# Arduino_SST39SF040_Programmer_Shield_202.net
KiCad netlist of a schematic drawn in EasyEDA
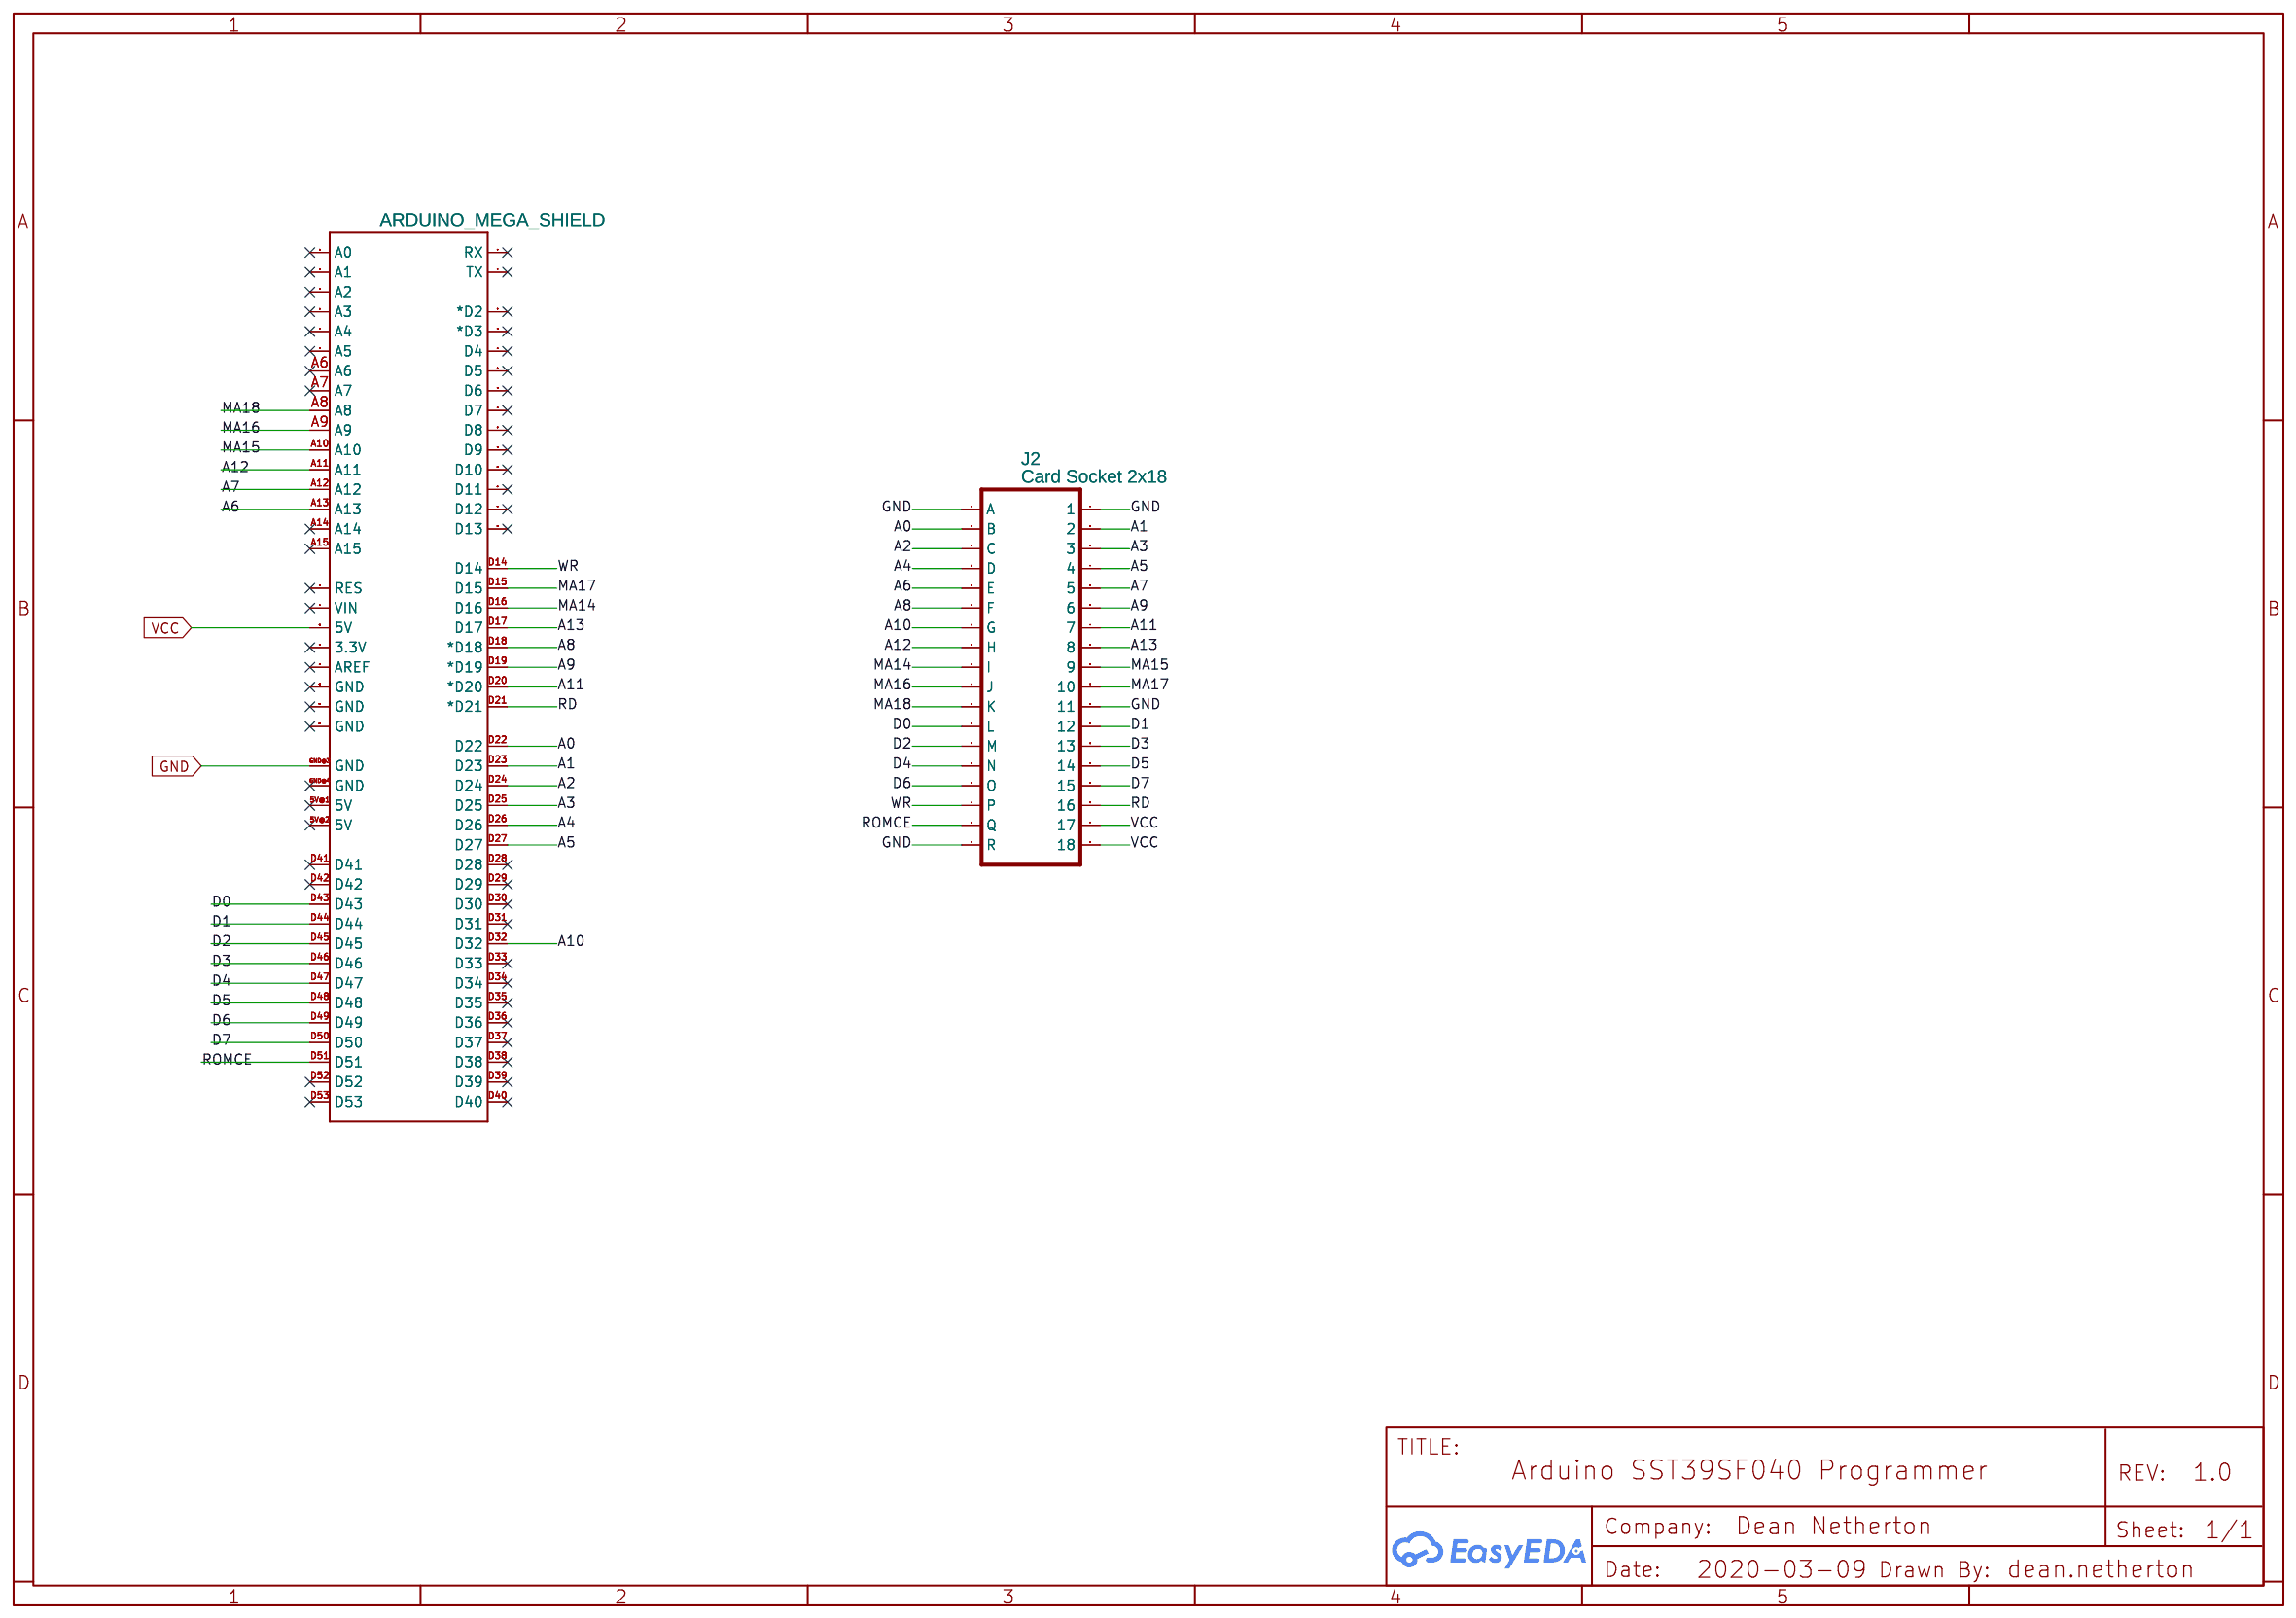
[diagram p0: schematic sheet]

(export (version "E")
  (design (tool "Eeschema 10.0.6"))
  (components
    (comp (ref "J2") (value "Card Socket 2x18") (libsource (lib "") (part "Card Socket 2x18")))
    (comp (ref "U2") (value "ARDUINO_MEGA_SHIELD") (libsource (lib "") (part "ARDUINO_MEGA_SHIELD")))
  )
  (nets
    (net (code "1") (name "/A0") (class "Default")
      (node (ref "J2") (pin "B") (pinfunction "B_B") (pintype "unspecified"))
      (node (ref "U2") (pin "D22") (pinfunction "D22_D22") (pintype "unspecified"))
    )
    (net (code "2") (name "/A1") (class "Default")
      (node (ref "J2") (pin "2") (pinfunction "2_2") (pintype "unspecified"))
      (node (ref "U2") (pin "D23") (pinfunction "D23_D23") (pintype "unspecified"))
    )
    (net (code "3") (name "/A2") (class "Default")
      (node (ref "J2") (pin "C") (pinfunction "C_C") (pintype "unspecified"))
      (node (ref "U2") (pin "D24") (pinfunction "D24_D24") (pintype "unspecified"))
    )
    (net (code "4") (name "/A3") (class "Default")
      (node (ref "J2") (pin "3") (pinfunction "3_3") (pintype "unspecified"))
      (node (ref "U2") (pin "D25") (pinfunction "D25_D25") (pintype "unspecified"))
    )
    (net (code "5") (name "/A4") (class "Default")
      (node (ref "J2") (pin "D") (pinfunction "D_D") (pintype "unspecified"))
      (node (ref "U2") (pin "D26") (pinfunction "D26_D26") (pintype "unspecified"))
    )
    (net (code "6") (name "/A5") (class "Default")
      (node (ref "J2") (pin "4") (pinfunction "4_4") (pintype "unspecified"))
      (node (ref "U2") (pin "D27") (pinfunction "D27_D27") (pintype "unspecified"))
    )
    (net (code "7") (name "/A6") (class "Default")
      (node (ref "J2") (pin "E") (pinfunction "E_E") (pintype "unspecified"))
      (node (ref "U2") (pin "A13") (pinfunction "A13_A13") (pintype "unspecified"))
    )
    (net (code "8") (name "/A7") (class "Default")
      (node (ref "J2") (pin "5") (pinfunction "5_5") (pintype "unspecified"))
      (node (ref "U2") (pin "A12") (pinfunction "A12_A12") (pintype "unspecified"))
    )
    (net (code "9") (name "/A8") (class "Default")
      (node (ref "J2") (pin "F") (pinfunction "F_F") (pintype "unspecified"))
      (node (ref "U2") (pin "D18") (pinfunction "*D18_D18") (pintype "unspecified"))
    )
    (net (code "10") (name "/A9") (class "Default")
      (node (ref "J2") (pin "6") (pinfunction "6_6") (pintype "unspecified"))
      (node (ref "U2") (pin "D19") (pinfunction "*D19_D19") (pintype "unspecified"))
    )
    (net (code "11") (name "/A10") (class "Default")
      (node (ref "J2") (pin "H") (pinfunction "G_H") (pintype "unspecified"))
      (node (ref "U2") (pin "D32") (pinfunction "D32_D32") (pintype "unspecified"))
    )
    (net (code "12") (name "/A11") (class "Default")
      (node (ref "J2") (pin "7") (pinfunction "7_7") (pintype "unspecified"))
      (node (ref "U2") (pin "D20") (pinfunction "*D20_D20") (pintype "unspecified"))
    )
    (net (code "13") (name "/A12") (class "Default")
      (node (ref "J2") (pin "J") (pinfunction "H_J") (pintype "unspecified"))
      (node (ref "U2") (pin "A11") (pinfunction "A11_A11") (pintype "unspecified"))
    )
    (net (code "14") (name "/A13") (class "Default")
      (node (ref "J2") (pin "8") (pinfunction "8_8") (pintype "unspecified"))
      (node (ref "U2") (pin "D17") (pinfunction "D17_D17") (pintype "unspecified"))
    )
    (net (code "15") (name "/D0") (class "Default")
      (node (ref "J2") (pin "N") (pinfunction "L_N") (pintype "unspecified"))
      (node (ref "U2") (pin "D43") (pinfunction "D43_D43") (pintype "unspecified"))
    )
    (net (code "16") (name "/D1") (class "Default")
      (node (ref "J2") (pin "12") (pinfunction "12_12") (pintype "unspecified"))
      (node (ref "U2") (pin "D44") (pinfunction "D44_D44") (pintype "unspecified"))
    )
    (net (code "17") (name "/D2") (class "Default")
      (node (ref "J2") (pin "P") (pinfunction "M_P") (pintype "unspecified"))
      (node (ref "U2") (pin "D45") (pinfunction "D45_D45") (pintype "unspecified"))
    )
    (net (code "18") (name "/D3") (class "Default")
      (node (ref "J2") (pin "13") (pinfunction "13_13") (pintype "unspecified"))
      (node (ref "U2") (pin "D46") (pinfunction "D46_D46") (pintype "unspecified"))
    )
    (net (code "19") (name "/D4") (class "Default")
      (node (ref "J2") (pin "R") (pinfunction "N_R") (pintype "unspecified"))
      (node (ref "U2") (pin "D47") (pinfunction "D47_D47") (pintype "unspecified"))
    )
    (net (code "20") (name "/D5") (class "Default")
      (node (ref "J2") (pin "14") (pinfunction "14_14") (pintype "unspecified"))
      (node (ref "U2") (pin "D48") (pinfunction "D48_D48") (pintype "unspecified"))
    )
    (net (code "21") (name "/D6") (class "Default")
      (node (ref "J2") (pin "S") (pinfunction "O_S") (pintype "unspecified"))
      (node (ref "U2") (pin "D49") (pinfunction "D49_D49") (pintype "unspecified"))
    )
    (net (code "22") (name "/D7") (class "Default")
      (node (ref "J2") (pin "15") (pinfunction "15_15") (pintype "unspecified"))
      (node (ref "U2") (pin "D50") (pinfunction "D50_D50") (pintype "unspecified"))
    )
    (net (code "23") (name "/MA14") (class "Default")
      (node (ref "J2") (pin "K") (pinfunction "I_K") (pintype "unspecified"))
      (node (ref "U2") (pin "D16") (pinfunction "D16_D16") (pintype "unspecified"))
    )
    (net (code "24") (name "/MA15") (class "Default")
      (node (ref "J2") (pin "9") (pinfunction "9_9") (pintype "unspecified"))
      (node (ref "U2") (pin "A10") (pinfunction "A10_A10") (pintype "unspecified"))
    )
    (net (code "25") (name "/MA16") (class "Default")
      (node (ref "J2") (pin "L") (pinfunction "J_L") (pintype "unspecified"))
      (node (ref "U2") (pin "A9") (pinfunction "A9_A9") (pintype "unspecified"))
    )
    (net (code "26") (name "/MA17") (class "Default")
      (node (ref "J2") (pin "10") (pinfunction "10_10") (pintype "unspecified"))
      (node (ref "U2") (pin "D15") (pinfunction "D15_D15") (pintype "unspecified"))
    )
    (net (code "27") (name "/MA18") (class "Default")
      (node (ref "J2") (pin "M") (pinfunction "K_M") (pintype "unspecified"))
      (node (ref "U2") (pin "A8") (pinfunction "A8_A8") (pintype "unspecified"))
    )
    (net (code "28") (name "/RD") (class "Default")
      (node (ref "J2") (pin "16") (pinfunction "16_16") (pintype "unspecified"))
      (node (ref "U2") (pin "D21") (pinfunction "*D21_D21") (pintype "unspecified"))
    )
    (net (code "29") (name "/ROMCE") (class "Default")
      (node (ref "J2") (pin "U") (pinfunction "Q_U") (pintype "unspecified"))
      (node (ref "U2") (pin "D51") (pinfunction "D51_D51") (pintype "unspecified"))
    )
    (net (code "30") (name "/WR") (class "Default")
      (node (ref "J2") (pin "T") (pinfunction "P_T") (pintype "unspecified"))
      (node (ref "U2") (pin "D14") (pinfunction "D14_D14") (pintype "unspecified"))
    )
    (net (code "31") (name "GND") (class "Default")
      (node (ref "J2") (pin "1") (pinfunction "1_1") (pintype "unspecified"))
      (node (ref "J2") (pin "11") (pinfunction "11_11") (pintype "unspecified"))
      (node (ref "J2") (pin "A") (pinfunction "A_A") (pintype "unspecified"))
      (node (ref "J2") (pin "V") (pinfunction "R_V") (pintype "unspecified"))
      (node (ref "U2") (pin "GND@3") (pinfunction "GND_GND@3") (pintype "unspecified"))
    )
    (net (code "32") (name "VCC") (class "Default")
      (node (ref "J2") (pin "17") (pinfunction "17_17") (pintype "unspecified"))
      (node (ref "J2") (pin "18") (pinfunction "18_18") (pintype "unspecified"))
      (node (ref "U2") (pin "5V@0") (pinfunction "5V_5V@0") (pintype "passive"))
    )
    (net (code "33") (name "unconnected-(U2-*D2-PadD2)") (class "Default")
      (node (ref "U2") (pin "D2") (pinfunction "*D2_D2") (pintype "unspecified+no_connect"))
    )
    (net (code "34") (name "unconnected-(U2-*D3-PadD3)") (class "Default")
      (node (ref "U2") (pin "D3") (pinfunction "*D3_D3") (pintype "unspecified+no_connect"))
    )
    (net (code "35") (name "unconnected-(U2-5V-Pad5V@1)") (class "Default")
      (node (ref "U2") (pin "5V@1") (pinfunction "5V_5V@1") (pintype "unspecified+no_connect"))
    )
    (net (code "36") (name "unconnected-(U2-5V-Pad5V@2)") (class "Default")
      (node (ref "U2") (pin "5V@2") (pinfunction "5V_5V@2") (pintype "unspecified+no_connect"))
    )
    (net (code "37") (name "unconnected-(U2-GND-PadGND@0)") (class "Default")
      (node (ref "U2") (pin "GND@0") (pinfunction "GND_GND@0") (pintype "unspecified+no_connect"))
    )
    (net (code "38") (name "unconnected-(U2-GND-PadGND@1)") (class "Default")
      (node (ref "U2") (pin "GND@1") (pinfunction "GND_GND@1") (pintype "unspecified+no_connect"))
    )
    (net (code "39") (name "unconnected-(U2-GND-PadGND@2)") (class "Default")
      (node (ref "U2") (pin "GND@2") (pinfunction "GND_GND@2") (pintype "unspecified+no_connect"))
    )
    (net (code "40") (name "unconnected-(U2-GND-PadGND@4)") (class "Default")
      (node (ref "U2") (pin "GND@4") (pinfunction "GND_GND@4") (pintype "unspecified+no_connect"))
    )
    (net (code "41") (name "unconnected-(U2-Pad3.3V)") (class "Default")
      (node (ref "U2") (pin "3.3V") (pinfunction "3.3V_3.3V") (pintype "unspecified+no_connect"))
    )
    (net (code "42") (name "unconnected-(U2-PadA0)") (class "Default")
      (node (ref "U2") (pin "A0") (pinfunction "A0_A0") (pintype "unspecified+no_connect"))
    )
    (net (code "43") (name "unconnected-(U2-PadA1)") (class "Default")
      (node (ref "U2") (pin "A1") (pinfunction "A1_A1") (pintype "unspecified+no_connect"))
    )
    (net (code "44") (name "unconnected-(U2-PadA2)") (class "Default")
      (node (ref "U2") (pin "A2") (pinfunction "A2_A2") (pintype "unspecified+no_connect"))
    )
    (net (code "45") (name "unconnected-(U2-PadA3)") (class "Default")
      (node (ref "U2") (pin "A3") (pinfunction "A3_A3") (pintype "unspecified+no_connect"))
    )
    (net (code "46") (name "unconnected-(U2-PadA4)") (class "Default")
      (node (ref "U2") (pin "A4") (pinfunction "A4_A4") (pintype "unspecified+no_connect"))
    )
    (net (code "47") (name "unconnected-(U2-PadA5)") (class "Default")
      (node (ref "U2") (pin "A5") (pinfunction "A5_A5") (pintype "unspecified+no_connect"))
    )
    (net (code "48") (name "unconnected-(U2-PadA6)") (class "Default")
      (node (ref "U2") (pin "A6") (pinfunction "A6_A6") (pintype "unspecified+no_connect"))
    )
    (net (code "49") (name "unconnected-(U2-PadA7)") (class "Default")
      (node (ref "U2") (pin "A7") (pinfunction "A7_A7") (pintype "unspecified+no_connect"))
    )
    (net (code "50") (name "unconnected-(U2-PadA14)") (class "Default")
      (node (ref "U2") (pin "A14") (pinfunction "A14_A14") (pintype "unspecified+no_connect"))
    )
    (net (code "51") (name "unconnected-(U2-PadA15)") (class "Default")
      (node (ref "U2") (pin "A15") (pinfunction "A15_A15") (pintype "unspecified+no_connect"))
    )
    (net (code "52") (name "unconnected-(U2-PadAREF)") (class "Default")
      (node (ref "U2") (pin "AREF") (pinfunction "AREF_AREF") (pintype "unspecified+no_connect"))
    )
    (net (code "53") (name "unconnected-(U2-PadD4)") (class "Default")
      (node (ref "U2") (pin "D4") (pinfunction "D4_D4") (pintype "unspecified+no_connect"))
    )
    (net (code "54") (name "unconnected-(U2-PadD5)") (class "Default")
      (node (ref "U2") (pin "D5") (pinfunction "D5_D5") (pintype "unspecified+no_connect"))
    )
    (net (code "55") (name "unconnected-(U2-PadD6)") (class "Default")
      (node (ref "U2") (pin "D6") (pinfunction "D6_D6") (pintype "unspecified+no_connect"))
    )
    (net (code "56") (name "unconnected-(U2-PadD7)") (class "Default")
      (node (ref "U2") (pin "D7") (pinfunction "D7_D7") (pintype "unspecified+no_connect"))
    )
    (net (code "57") (name "unconnected-(U2-PadD8)") (class "Default")
      (node (ref "U2") (pin "D8") (pinfunction "D8_D8") (pintype "unspecified+no_connect"))
    )
    (net (code "58") (name "unconnected-(U2-PadD9)") (class "Default")
      (node (ref "U2") (pin "D9") (pinfunction "D9_D9") (pintype "unspecified+no_connect"))
    )
    (net (code "59") (name "unconnected-(U2-PadD10)") (class "Default")
      (node (ref "U2") (pin "D10") (pinfunction "D10_D10") (pintype "unspecified+no_connect"))
    )
    (net (code "60") (name "unconnected-(U2-PadD11)") (class "Default")
      (node (ref "U2") (pin "D11") (pinfunction "D11_D11") (pintype "unspecified+no_connect"))
    )
    (net (code "61") (name "unconnected-(U2-PadD12)") (class "Default")
      (node (ref "U2") (pin "D12") (pinfunction "D12_D12") (pintype "unspecified+no_connect"))
    )
    (net (code "62") (name "unconnected-(U2-PadD13)") (class "Default")
      (node (ref "U2") (pin "D13") (pinfunction "D13_D13") (pintype "unspecified+no_connect"))
    )
    (net (code "63") (name "unconnected-(U2-PadD28)") (class "Default")
      (node (ref "U2") (pin "D28") (pinfunction "D28_D28") (pintype "unspecified+no_connect"))
    )
    (net (code "64") (name "unconnected-(U2-PadD29)") (class "Default")
      (node (ref "U2") (pin "D29") (pinfunction "D29_D29") (pintype "unspecified+no_connect"))
    )
    (net (code "65") (name "unconnected-(U2-PadD30)") (class "Default")
      (node (ref "U2") (pin "D30") (pinfunction "D30_D30") (pintype "unspecified+no_connect"))
    )
    (net (code "66") (name "unconnected-(U2-PadD31)") (class "Default")
      (node (ref "U2") (pin "D31") (pinfunction "D31_D31") (pintype "unspecified+no_connect"))
    )
    (net (code "67") (name "unconnected-(U2-PadD33)") (class "Default")
      (node (ref "U2") (pin "D33") (pinfunction "D33_D33") (pintype "unspecified+no_connect"))
    )
    (net (code "68") (name "unconnected-(U2-PadD34)") (class "Default")
      (node (ref "U2") (pin "D34") (pinfunction "D34_D34") (pintype "unspecified+no_connect"))
    )
    (net (code "69") (name "unconnected-(U2-PadD35)") (class "Default")
      (node (ref "U2") (pin "D35") (pinfunction "D35_D35") (pintype "unspecified+no_connect"))
    )
    (net (code "70") (name "unconnected-(U2-PadD36)") (class "Default")
      (node (ref "U2") (pin "D36") (pinfunction "D36_D36") (pintype "unspecified+no_connect"))
    )
    (net (code "71") (name "unconnected-(U2-PadD37)") (class "Default")
      (node (ref "U2") (pin "D37") (pinfunction "D37_D37") (pintype "unspecified+no_connect"))
    )
    (net (code "72") (name "unconnected-(U2-PadD38)") (class "Default")
      (node (ref "U2") (pin "D38") (pinfunction "D38_D38") (pintype "unspecified+no_connect"))
    )
    (net (code "73") (name "unconnected-(U2-PadD39)") (class "Default")
      (node (ref "U2") (pin "D39") (pinfunction "D39_D39") (pintype "unspecified+no_connect"))
    )
    (net (code "74") (name "unconnected-(U2-PadD40)") (class "Default")
      (node (ref "U2") (pin "D40") (pinfunction "D40_D40") (pintype "unspecified+no_connect"))
    )
    (net (code "75") (name "unconnected-(U2-PadD41)") (class "Default")
      (node (ref "U2") (pin "D41") (pinfunction "D41_D41") (pintype "unspecified+no_connect"))
    )
    (net (code "76") (name "unconnected-(U2-PadD42)") (class "Default")
      (node (ref "U2") (pin "D42") (pinfunction "D42_D42") (pintype "unspecified+no_connect"))
    )
    (net (code "77") (name "unconnected-(U2-PadD52)") (class "Default")
      (node (ref "U2") (pin "D52") (pinfunction "D52_D52") (pintype "unspecified+no_connect"))
    )
    (net (code "78") (name "unconnected-(U2-PadD53)") (class "Default")
      (node (ref "U2") (pin "D53") (pinfunction "D53_D53") (pintype "unspecified+no_connect"))
    )
    (net (code "79") (name "unconnected-(U2-PadRES)") (class "Default")
      (node (ref "U2") (pin "RES") (pinfunction "RES_RES") (pintype "unspecified+no_connect"))
    )
    (net (code "80") (name "unconnected-(U2-PadRX)") (class "Default")
      (node (ref "U2") (pin "RX") (pinfunction "RX_RX") (pintype "unspecified+no_connect"))
    )
    (net (code "81") (name "unconnected-(U2-PadTX)") (class "Default")
      (node (ref "U2") (pin "TX") (pinfunction "TX_TX") (pintype "unspecified+no_connect"))
    )
    (net (code "82") (name "unconnected-(U2-PadVIN)") (class "Default")
      (node (ref "U2") (pin "VIN") (pinfunction "VIN_VIN") (pintype "unspecified+no_connect"))
    )
  )
)
